# S603X.net
KiCad netlist of a schematic drawn in EAGLE
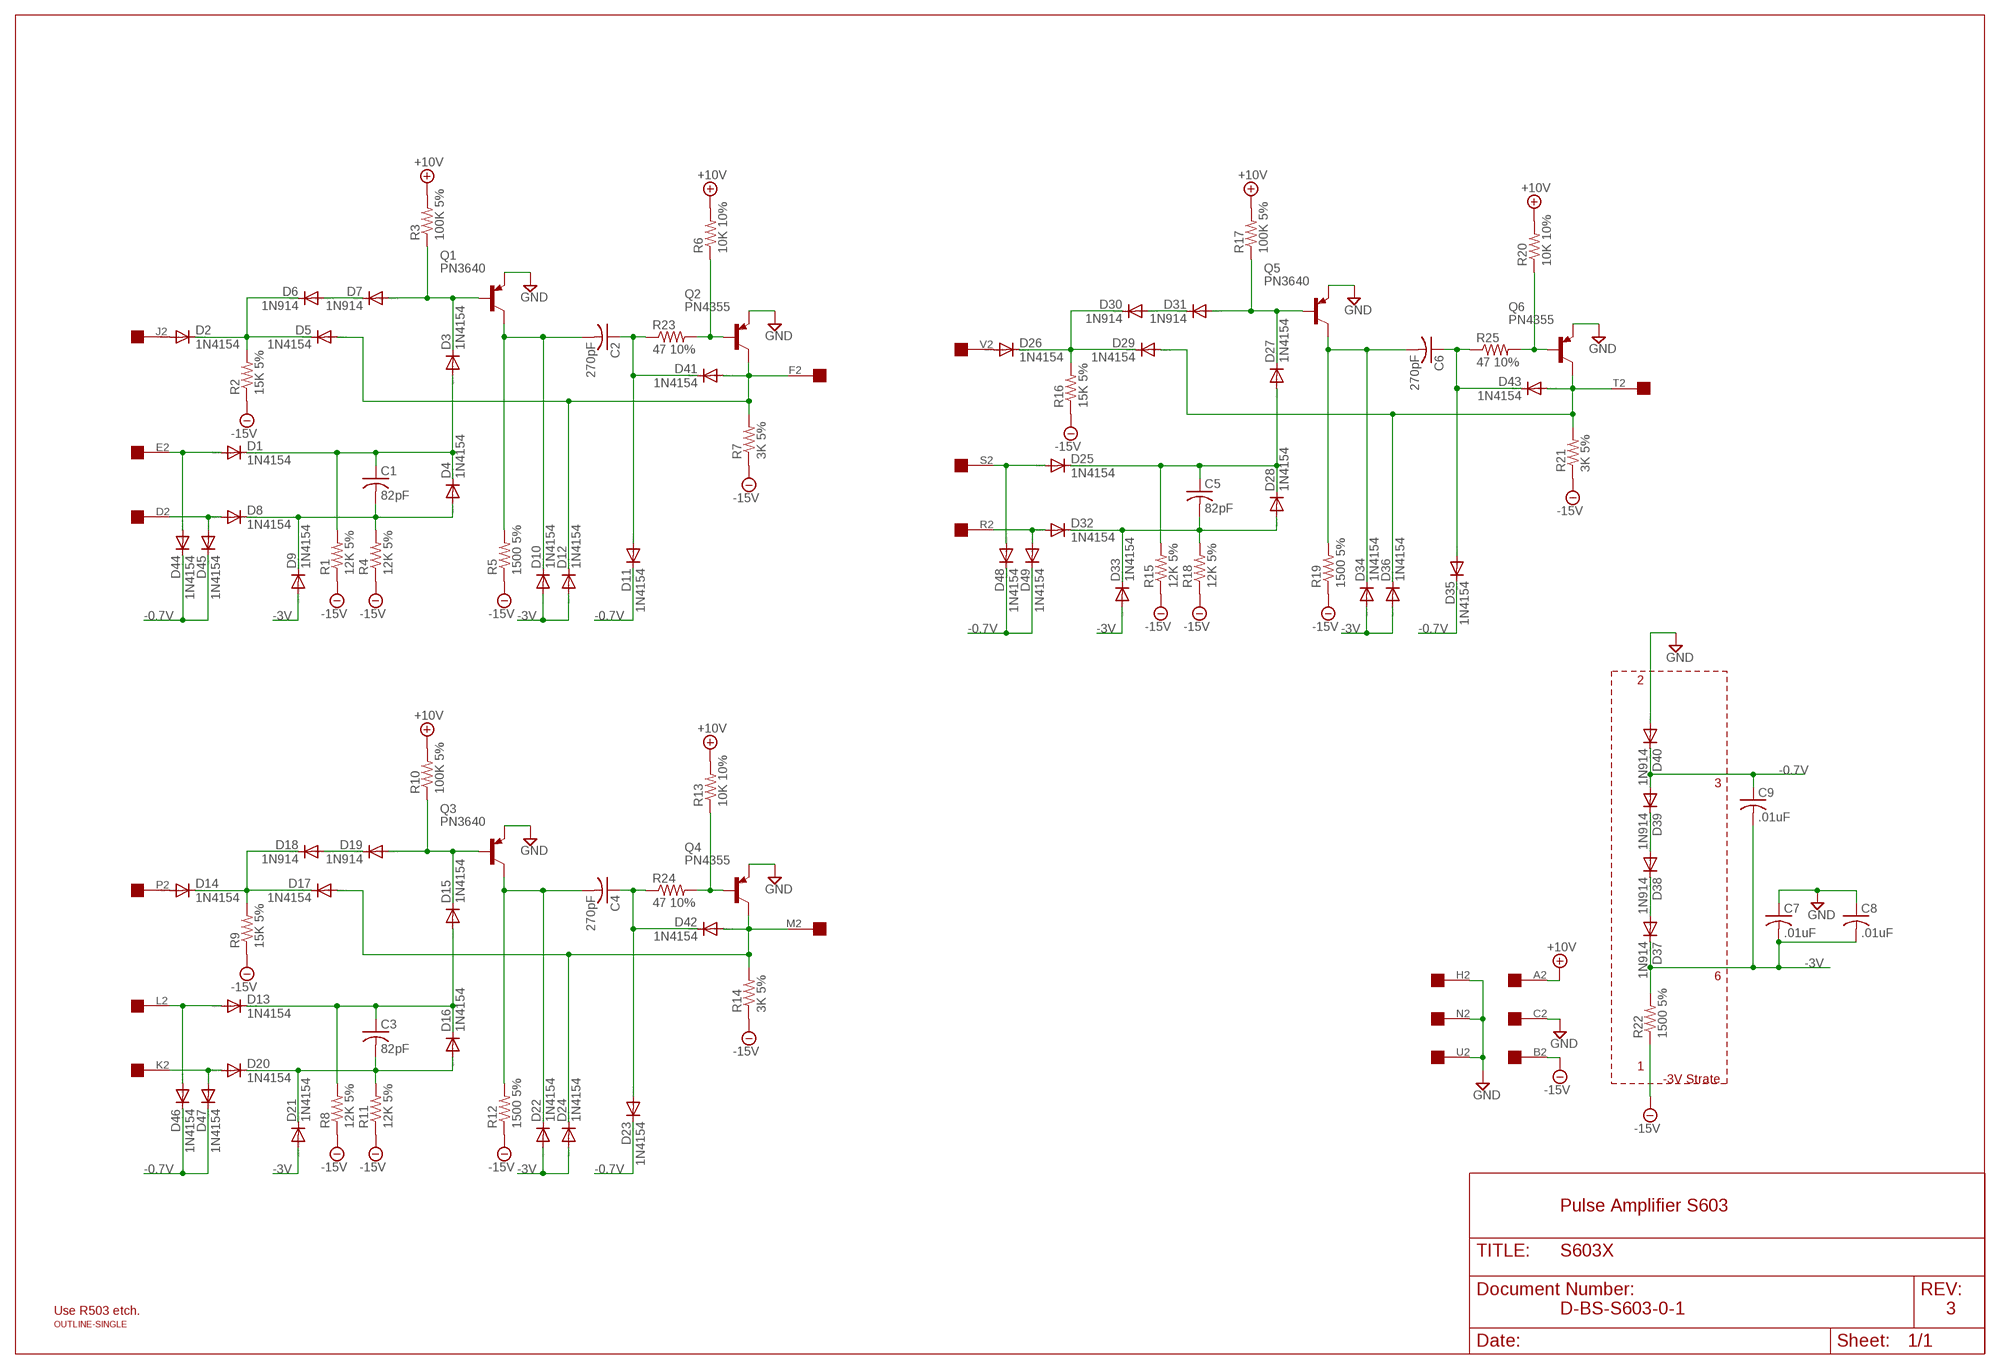
[diagram p0: schematic, sheet 1]

(export (version "E")
  (design (tool "Eeschema 10.0.6"))
  (components
    (comp (ref "C1")
      (value "82pF")
      (footprint "eagle-import:C050-025X075")
      (libsource (lib "eagle-import") (part "C-US050-025X075"))
    )
    (comp (ref "C2")
      (value "270pF")
      (footprint "eagle-import:C050-025X075")
      (libsource (lib "eagle-import") (part "C-US050-025X075"))
    )
    (comp (ref "C3")
      (value "82pF")
      (footprint "eagle-import:C050-025X075")
      (libsource (lib "eagle-import") (part "C-US050-025X075"))
    )
    (comp (ref "C4")
      (value "270pF")
      (footprint "eagle-import:C050-025X075")
      (libsource (lib "eagle-import") (part "C-US050-025X075"))
    )
    (comp (ref "C5")
      (value "82pF")
      (footprint "eagle-import:C050-025X075")
      (libsource (lib "eagle-import") (part "C-US050-025X075"))
    )
    (comp (ref "C6")
      (value "270pF")
      (footprint "eagle-import:C050-025X075")
      (libsource (lib "eagle-import") (part "C-US050-025X075"))
    )
    (comp (ref "C7")
      (value ".01uF")
      (footprint "eagle-import:C050-025X075")
      (libsource (lib "eagle-import") (part "C-US050-025X075"))
    )
    (comp (ref "C8")
      (value ".01uF")
      (footprint "eagle-import:C050-025X075")
      (libsource (lib "eagle-import") (part "C-US050-025X075"))
    )
    (comp (ref "C9")
      (value ".01uF")
      (footprint "eagle-import:C050-025X075")
      (libsource (lib "eagle-import") (part "C-US050-025X075"))
    )
    (comp (ref "D1")
      (value "1N4154")
      (footprint "eagle-import:DO35-10")
      (libsource (lib "eagle-import") (part "1N4148DO35-10"))
    )
    (comp (ref "D2")
      (value "1N4154")
      (footprint "eagle-import:DO35-10")
      (libsource (lib "eagle-import") (part "1N4148DO35-10"))
    )
    (comp (ref "D3")
      (value "1N4154")
      (footprint "eagle-import:DO35-10")
      (libsource (lib "eagle-import") (part "1N4148DO35-10"))
    )
    (comp (ref "D4")
      (value "1N4154")
      (footprint "eagle-import:DO35-10")
      (libsource (lib "eagle-import") (part "1N4148DO35-10"))
    )
    (comp (ref "D5")
      (value "1N4154")
      (footprint "eagle-import:DO35-10")
      (libsource (lib "eagle-import") (part "1N4148DO35-10"))
    )
    (comp (ref "D6")
      (value "1N914")
      (footprint "eagle-import:DO35-10")
      (libsource (lib "eagle-import") (part "1N4148DO35-10"))
    )
    (comp (ref "D7")
      (value "1N914")
      (footprint "eagle-import:DO35-10")
      (libsource (lib "eagle-import") (part "1N4148DO35-10"))
    )
    (comp (ref "D8")
      (value "1N4154")
      (footprint "eagle-import:DO35-10")
      (libsource (lib "eagle-import") (part "1N4148DO35-10"))
    )
    (comp (ref "D9")
      (value "1N4154")
      (footprint "eagle-import:DO35-10")
      (libsource (lib "eagle-import") (part "1N4148DO35-10"))
    )
    (comp (ref "D10")
      (value "1N4154")
      (footprint "eagle-import:DO35-10")
      (libsource (lib "eagle-import") (part "1N4148DO35-10"))
    )
    (comp (ref "D11")
      (value "1N4154")
      (footprint "eagle-import:DO35-10")
      (libsource (lib "eagle-import") (part "1N4148DO35-10"))
    )
    (comp (ref "D12")
      (value "1N4154")
      (footprint "eagle-import:DO35-10")
      (libsource (lib "eagle-import") (part "1N4148DO35-10"))
    )
    (comp (ref "D13")
      (value "1N4154")
      (footprint "eagle-import:DO35-10")
      (libsource (lib "eagle-import") (part "1N4148DO35-10"))
    )
    (comp (ref "D14")
      (value "1N4154")
      (footprint "eagle-import:DO35-10")
      (libsource (lib "eagle-import") (part "1N4148DO35-10"))
    )
    (comp (ref "D15")
      (value "1N4154")
      (footprint "eagle-import:DO35-10")
      (libsource (lib "eagle-import") (part "1N4148DO35-10"))
    )
    (comp (ref "D16")
      (value "1N4154")
      (footprint "eagle-import:DO35-10")
      (libsource (lib "eagle-import") (part "1N4148DO35-10"))
    )
    (comp (ref "D17")
      (value "1N4154")
      (footprint "eagle-import:DO35-10")
      (libsource (lib "eagle-import") (part "1N4148DO35-10"))
    )
    (comp (ref "D18")
      (value "1N914")
      (footprint "eagle-import:DO35-10")
      (libsource (lib "eagle-import") (part "1N4148DO35-10"))
    )
    (comp (ref "D19")
      (value "1N914")
      (footprint "eagle-import:DO35-10")
      (libsource (lib "eagle-import") (part "1N4148DO35-10"))
    )
    (comp (ref "D20")
      (value "1N4154")
      (footprint "eagle-import:DO35-10")
      (libsource (lib "eagle-import") (part "1N4148DO35-10"))
    )
    (comp (ref "D21")
      (value "1N4154")
      (footprint "eagle-import:DO35-10")
      (libsource (lib "eagle-import") (part "1N4148DO35-10"))
    )
    (comp (ref "D22")
      (value "1N4154")
      (footprint "eagle-import:DO35-10")
      (libsource (lib "eagle-import") (part "1N4148DO35-10"))
    )
    (comp (ref "D23")
      (value "1N4154")
      (footprint "eagle-import:DO35-10")
      (libsource (lib "eagle-import") (part "1N4148DO35-10"))
    )
    (comp (ref "D24")
      (value "1N4154")
      (footprint "eagle-import:DO35-10")
      (libsource (lib "eagle-import") (part "1N4148DO35-10"))
    )
    (comp (ref "D25")
      (value "1N4154")
      (footprint "eagle-import:DO35-10")
      (libsource (lib "eagle-import") (part "1N4148DO35-10"))
    )
    (comp (ref "D26")
      (value "1N4154")
      (footprint "eagle-import:DO35-10")
      (libsource (lib "eagle-import") (part "1N4148DO35-10"))
    )
    (comp (ref "D27")
      (value "1N4154")
      (footprint "eagle-import:DO35-10")
      (libsource (lib "eagle-import") (part "1N4148DO35-10"))
    )
    (comp (ref "D28")
      (value "1N4154")
      (footprint "eagle-import:DO35-10")
      (libsource (lib "eagle-import") (part "1N4148DO35-10"))
    )
    (comp (ref "D29")
      (value "1N4154")
      (footprint "eagle-import:DO35-10")
      (libsource (lib "eagle-import") (part "1N4148DO35-10"))
    )
    (comp (ref "D30")
      (value "1N914")
      (footprint "eagle-import:DO35-10")
      (libsource (lib "eagle-import") (part "1N4148DO35-10"))
    )
    (comp (ref "D31")
      (value "1N914")
      (footprint "eagle-import:DO35-10")
      (libsource (lib "eagle-import") (part "1N4148DO35-10"))
    )
    (comp (ref "D32")
      (value "1N4154")
      (footprint "eagle-import:DO35-10")
      (libsource (lib "eagle-import") (part "1N4148DO35-10"))
    )
    (comp (ref "D33")
      (value "1N4154")
      (footprint "eagle-import:DO35-10")
      (libsource (lib "eagle-import") (part "1N4148DO35-10"))
    )
    (comp (ref "D34")
      (value "1N4154")
      (footprint "eagle-import:DO35-10")
      (libsource (lib "eagle-import") (part "1N4148DO35-10"))
    )
    (comp (ref "D35")
      (value "1N4154")
      (footprint "eagle-import:DO35-10")
      (libsource (lib "eagle-import") (part "1N4148DO35-10"))
    )
    (comp (ref "D36")
      (value "1N4154")
      (footprint "eagle-import:DO35-10")
      (libsource (lib "eagle-import") (part "1N4148DO35-10"))
    )
    (comp (ref "D37")
      (value "1N914")
      (footprint "eagle-import:DO35-10")
      (libsource (lib "eagle-import") (part "1N4148DO35-10"))
    )
    (comp (ref "D38")
      (value "1N914")
      (footprint "eagle-import:DO35-10")
      (libsource (lib "eagle-import") (part "1N4148DO35-10"))
    )
    (comp (ref "D39")
      (value "1N914")
      (footprint "eagle-import:DO35-10")
      (libsource (lib "eagle-import") (part "1N4148DO35-10"))
    )
    (comp (ref "D40")
      (value "1N914")
      (footprint "eagle-import:DO35-10")
      (libsource (lib "eagle-import") (part "1N4148DO35-10"))
    )
    (comp (ref "D41")
      (value "1N4154")
      (footprint "eagle-import:DO35-10")
      (libsource (lib "eagle-import") (part "1N4148DO35-10"))
    )
    (comp (ref "D42")
      (value "1N4154")
      (footprint "eagle-import:DO35-10")
      (libsource (lib "eagle-import") (part "1N4148DO35-10"))
    )
    (comp (ref "D43")
      (value "1N4154")
      (footprint "eagle-import:DO35-10")
      (libsource (lib "eagle-import") (part "1N4148DO35-10"))
    )
    (comp (ref "D44")
      (value "1N4154")
      (footprint "eagle-import:DO35-10")
      (libsource (lib "eagle-import") (part "1N4148DO35-10"))
    )
    (comp (ref "D45")
      (value "1N4154")
      (footprint "eagle-import:DO35-10")
      (libsource (lib "eagle-import") (part "1N4148DO35-10"))
    )
    (comp (ref "D46")
      (value "1N4154")
      (footprint "eagle-import:DO35-10")
      (libsource (lib "eagle-import") (part "1N4148DO35-10"))
    )
    (comp (ref "D47")
      (value "1N4154")
      (footprint "eagle-import:DO35-10")
      (libsource (lib "eagle-import") (part "1N4148DO35-10"))
    )
    (comp (ref "D48")
      (value "1N4154")
      (footprint "eagle-import:DO35-10")
      (libsource (lib "eagle-import") (part "1N4148DO35-10"))
    )
    (comp (ref "D49")
      (value "1N4154")
      (footprint "eagle-import:DO35-10")
      (libsource (lib "eagle-import") (part "1N4148DO35-10"))
    )
    (comp (ref "Q1")
      (value "PN3640")
      (footprint "eagle-import:TO39")
      (libsource (lib "eagle-import") (part "2N2904"))
    )
    (comp (ref "Q2")
      (value "PN4355")
      (footprint "eagle-import:TO39")
      (libsource (lib "eagle-import") (part "2N2904"))
    )
    (comp (ref "Q3")
      (value "PN3640")
      (footprint "eagle-import:TO39")
      (libsource (lib "eagle-import") (part "2N2904"))
    )
    (comp (ref "Q4")
      (value "PN4355")
      (footprint "eagle-import:TO39")
      (libsource (lib "eagle-import") (part "2N2904"))
    )
    (comp (ref "Q5")
      (value "PN3640")
      (footprint "eagle-import:TO39")
      (libsource (lib "eagle-import") (part "2N2904"))
    )
    (comp (ref "Q6")
      (value "PN4355")
      (footprint "eagle-import:TO39")
      (libsource (lib "eagle-import") (part "2N2904"))
    )
    (comp (ref "R1")
      (value "12K 5%")
      (footprint "eagle-import:0207_10")
      (libsource (lib "eagle-import") (part "R-US_0207/10"))
    )
    (comp (ref "R2")
      (value "15K 5%")
      (footprint "eagle-import:0207_10")
      (libsource (lib "eagle-import") (part "R-US_0207/10"))
    )
    (comp (ref "R3")
      (value "100K 5%")
      (footprint "eagle-import:0207_10")
      (libsource (lib "eagle-import") (part "R-US_0207/10"))
    )
    (comp (ref "R4")
      (value "12K 5%")
      (footprint "eagle-import:0207_10")
      (libsource (lib "eagle-import") (part "R-US_0207/10"))
    )
    (comp (ref "R5")
      (value "1500 5%")
      (footprint "eagle-import:0207_10")
      (libsource (lib "eagle-import") (part "R-US_0207/10"))
    )
    (comp (ref "R6")
      (value "10K 10%")
      (footprint "eagle-import:0207_10")
      (libsource (lib "eagle-import") (part "R-US_0207/10"))
    )
    (comp (ref "R7")
      (value "3K 5%")
      (footprint "eagle-import:0207_10")
      (libsource (lib "eagle-import") (part "R-US_0207/10"))
    )
    (comp (ref "R8")
      (value "12K 5%")
      (footprint "eagle-import:0207_10")
      (libsource (lib "eagle-import") (part "R-US_0207/10"))
    )
    (comp (ref "R9")
      (value "15K 5%")
      (footprint "eagle-import:0207_10")
      (libsource (lib "eagle-import") (part "R-US_0207/10"))
    )
    (comp (ref "R10")
      (value "100K 5%")
      (footprint "eagle-import:0207_10")
      (libsource (lib "eagle-import") (part "R-US_0207/10"))
    )
    (comp (ref "R11")
      (value "12K 5%")
      (footprint "eagle-import:0207_10")
      (libsource (lib "eagle-import") (part "R-US_0207/10"))
    )
    (comp (ref "R12")
      (value "1500 5%")
      (footprint "eagle-import:0207_10")
      (libsource (lib "eagle-import") (part "R-US_0207/10"))
    )
    (comp (ref "R13")
      (value "10K 10%")
      (footprint "eagle-import:0207_10")
      (libsource (lib "eagle-import") (part "R-US_0207/10"))
    )
    (comp (ref "R14")
      (value "3K 5%")
      (footprint "eagle-import:0207_10")
      (libsource (lib "eagle-import") (part "R-US_0207/10"))
    )
    (comp (ref "R15")
      (value "12K 5%")
      (footprint "eagle-import:0207_10")
      (libsource (lib "eagle-import") (part "R-US_0207/10"))
    )
    (comp (ref "R16")
      (value "15K 5%")
      (footprint "eagle-import:0207_10")
      (libsource (lib "eagle-import") (part "R-US_0207/10"))
    )
    (comp (ref "R17")
      (value "100K 5%")
      (footprint "eagle-import:0207_10")
      (libsource (lib "eagle-import") (part "R-US_0207/10"))
    )
    (comp (ref "R18")
      (value "12K 5%")
      (footprint "eagle-import:0207_10")
      (libsource (lib "eagle-import") (part "R-US_0207/10"))
    )
    (comp (ref "R19")
      (value "1500 5%")
      (footprint "eagle-import:0207_10")
      (libsource (lib "eagle-import") (part "R-US_0207/10"))
    )
    (comp (ref "R20")
      (value "10K 10%")
      (footprint "eagle-import:0207_10")
      (libsource (lib "eagle-import") (part "R-US_0207/10"))
    )
    (comp (ref "R21")
      (value "3K 5%")
      (footprint "eagle-import:0207_10")
      (libsource (lib "eagle-import") (part "R-US_0207/10"))
    )
    (comp (ref "R22")
      (value "1500 5%")
      (footprint "eagle-import:0207_10")
      (libsource (lib "eagle-import") (part "R-US_0207/10"))
    )
    (comp (ref "R23")
      (value "47 10%")
      (footprint "eagle-import:0207_10")
      (libsource (lib "eagle-import") (part "R-US_0207/10"))
    )
    (comp (ref "R24")
      (value "47 10%")
      (footprint "eagle-import:0207_10")
      (libsource (lib "eagle-import") (part "R-US_0207/10"))
    )
    (comp (ref "R25")
      (value "47 10%")
      (footprint "eagle-import:0207_10")
      (libsource (lib "eagle-import") (part "R-US_0207/10"))
    )
    (comp (ref "U$1")
      (value "OUTLINE-SINGLE")
      (footprint "eagle-import:SINGLE")
      (libsource (lib "eagle-import") (part "OUTLINE-SINGLE"))
    )
    (comp (ref "U$2")
      (value "EDGE-1")
      (footprint "eagle-import:EDGE-CON1")
      (libsource (lib "eagle-import") (part "EDGE-1"))
    )
  )
  (nets
    (net (code "1") (name "+10V") (class "Default")
      (node (ref "R10") (pin "2") (pinfunction "2_2") (pintype "passive"))
      (node (ref "R13") (pin "2") (pinfunction "2_2") (pintype "passive"))
      (node (ref "R17") (pin "2") (pinfunction "2_2") (pintype "passive"))
      (node (ref "R20") (pin "2") (pinfunction "2_2") (pintype "passive"))
      (node (ref "R3") (pin "2") (pinfunction "2_2") (pintype "passive"))
      (node (ref "R6") (pin "2") (pinfunction "2_2") (pintype "passive"))
      (node (ref "U$2") (pin "A2") (pinfunction "1_A2") (pintype "bidirectional"))
    )
    (net (code "2") (name "-15V") (class "Default")
      (node (ref "R1") (pin "1") (pinfunction "1_1") (pintype "passive"))
      (node (ref "R11") (pin "1") (pinfunction "1_1") (pintype "passive"))
      (node (ref "R12") (pin "1") (pinfunction "1_1") (pintype "passive"))
      (node (ref "R14") (pin "1") (pinfunction "1_1") (pintype "passive"))
      (node (ref "R15") (pin "1") (pinfunction "1_1") (pintype "passive"))
      (node (ref "R16") (pin "1") (pinfunction "1_1") (pintype "passive"))
      (node (ref "R18") (pin "1") (pinfunction "1_1") (pintype "passive"))
      (node (ref "R19") (pin "1") (pinfunction "1_1") (pintype "passive"))
      (node (ref "R2") (pin "1") (pinfunction "1_1") (pintype "passive"))
      (node (ref "R21") (pin "1") (pinfunction "1_1") (pintype "passive"))
      (node (ref "R22") (pin "1") (pinfunction "1_1") (pintype "passive"))
      (node (ref "R4") (pin "1") (pinfunction "1_1") (pintype "passive"))
      (node (ref "R5") (pin "1") (pinfunction "1_1") (pintype "passive"))
      (node (ref "R7") (pin "1") (pinfunction "1_1") (pintype "passive"))
      (node (ref "R8") (pin "1") (pinfunction "1_1") (pintype "passive"))
      (node (ref "R9") (pin "1") (pinfunction "1_1") (pintype "passive"))
      (node (ref "U$2") (pin "B2") (pinfunction "1_B2") (pintype "bidirectional"))
    )
    (net (code "3") (name "/-0.7V") (class "Default")
      (node (ref "C9") (pin "1") (pinfunction "1_1") (pintype "passive"))
      (node (ref "D11") (pin "C") (pinfunction "C_C") (pintype "passive"))
      (node (ref "D23") (pin "C") (pinfunction "C_C") (pintype "passive"))
      (node (ref "D35") (pin "C") (pinfunction "C_C") (pintype "passive"))
      (node (ref "D39") (pin "A") (pinfunction "A_A") (pintype "passive"))
      (node (ref "D40") (pin "C") (pinfunction "C_C") (pintype "passive"))
      (node (ref "D44") (pin "C") (pinfunction "C_C") (pintype "passive"))
      (node (ref "D45") (pin "C") (pinfunction "C_C") (pintype "passive"))
      (node (ref "D46") (pin "C") (pinfunction "C_C") (pintype "passive"))
      (node (ref "D47") (pin "C") (pinfunction "C_C") (pintype "passive"))
      (node (ref "D48") (pin "C") (pinfunction "C_C") (pintype "passive"))
      (node (ref "D49") (pin "C") (pinfunction "C_C") (pintype "passive"))
    )
    (net (code "4") (name "/-3V") (class "Default")
      (node (ref "C7") (pin "2") (pinfunction "2_2") (pintype "passive"))
      (node (ref "C8") (pin "2") (pinfunction "2_2") (pintype "passive"))
      (node (ref "C9") (pin "2") (pinfunction "2_2") (pintype "passive"))
      (node (ref "D10") (pin "A") (pinfunction "A_A") (pintype "passive"))
      (node (ref "D12") (pin "A") (pinfunction "A_A") (pintype "passive"))
      (node (ref "D21") (pin "A") (pinfunction "A_A") (pintype "passive"))
      (node (ref "D22") (pin "A") (pinfunction "A_A") (pintype "passive"))
      (node (ref "D24") (pin "A") (pinfunction "A_A") (pintype "passive"))
      (node (ref "D33") (pin "A") (pinfunction "A_A") (pintype "passive"))
      (node (ref "D34") (pin "A") (pinfunction "A_A") (pintype "passive"))
      (node (ref "D36") (pin "A") (pinfunction "A_A") (pintype "passive"))
      (node (ref "D37") (pin "C") (pinfunction "C_C") (pintype "passive"))
      (node (ref "D9") (pin "A") (pinfunction "A_A") (pintype "passive"))
      (node (ref "R22") (pin "2") (pinfunction "2_2") (pintype "passive"))
    )
    (net (code "5") (name "GND") (class "Default")
      (node (ref "C7") (pin "1") (pinfunction "1_1") (pintype "passive"))
      (node (ref "C8") (pin "1") (pinfunction "1_1") (pintype "passive"))
      (node (ref "D40") (pin "A") (pinfunction "A_A") (pintype "passive"))
      (node (ref "Q1") (pin "1") (pinfunction "E_1") (pintype "passive"))
      (node (ref "Q2") (pin "1") (pinfunction "E_1") (pintype "passive"))
      (node (ref "Q3") (pin "1") (pinfunction "E_1") (pintype "passive"))
      (node (ref "Q4") (pin "1") (pinfunction "E_1") (pintype "passive"))
      (node (ref "Q5") (pin "1") (pinfunction "E_1") (pintype "passive"))
      (node (ref "Q6") (pin "1") (pinfunction "E_1") (pintype "passive"))
      (node (ref "U$2") (pin "C2") (pinfunction "1_C2") (pintype "bidirectional"))
      (node (ref "U$2") (pin "H2") (pinfunction "1_H2") (pintype "bidirectional"))
      (node (ref "U$2") (pin "N2") (pinfunction "1_N2") (pintype "bidirectional"))
      (node (ref "U$2") (pin "U2") (pinfunction "1_U2") (pintype "bidirectional"))
    )
    (net (code "6") (name "Net-(C1-Pad1)") (class "Default")
      (node (ref "C1") (pin "1") (pinfunction "1_1") (pintype "passive"))
      (node (ref "D1") (pin "C") (pinfunction "C_C") (pintype "passive"))
      (node (ref "D3") (pin "A") (pinfunction "A_A") (pintype "passive"))
      (node (ref "D4") (pin "C") (pinfunction "C_C") (pintype "passive"))
      (node (ref "R1") (pin "2") (pinfunction "2_2") (pintype "passive"))
    )
    (net (code "7") (name "Net-(C1-Pad2)") (class "Default")
      (node (ref "C1") (pin "2") (pinfunction "2_2") (pintype "passive"))
      (node (ref "D4") (pin "A") (pinfunction "A_A") (pintype "passive"))
      (node (ref "D8") (pin "C") (pinfunction "C_C") (pintype "passive"))
      (node (ref "D9") (pin "C") (pinfunction "C_C") (pintype "passive"))
      (node (ref "R4") (pin "2") (pinfunction "2_2") (pintype "passive"))
    )
    (net (code "8") (name "Net-(C2-Pad1)") (class "Default")
      (node (ref "C2") (pin "1") (pinfunction "1_1") (pintype "passive"))
      (node (ref "D11") (pin "A") (pinfunction "A_A") (pintype "passive"))
      (node (ref "D41") (pin "C") (pinfunction "C_C") (pintype "passive"))
      (node (ref "R23") (pin "1") (pinfunction "1_1") (pintype "passive"))
    )
    (net (code "9") (name "Net-(C3-Pad1)") (class "Default")
      (node (ref "C3") (pin "1") (pinfunction "1_1") (pintype "passive"))
      (node (ref "D13") (pin "C") (pinfunction "C_C") (pintype "passive"))
      (node (ref "D15") (pin "A") (pinfunction "A_A") (pintype "passive"))
      (node (ref "D16") (pin "C") (pinfunction "C_C") (pintype "passive"))
      (node (ref "R8") (pin "2") (pinfunction "2_2") (pintype "passive"))
    )
    (net (code "10") (name "Net-(C3-Pad2)") (class "Default")
      (node (ref "C3") (pin "2") (pinfunction "2_2") (pintype "passive"))
      (node (ref "D16") (pin "A") (pinfunction "A_A") (pintype "passive"))
      (node (ref "D20") (pin "C") (pinfunction "C_C") (pintype "passive"))
      (node (ref "D21") (pin "C") (pinfunction "C_C") (pintype "passive"))
      (node (ref "R11") (pin "2") (pinfunction "2_2") (pintype "passive"))
    )
    (net (code "11") (name "Net-(C4-Pad1)") (class "Default")
      (node (ref "C4") (pin "1") (pinfunction "1_1") (pintype "passive"))
      (node (ref "D23") (pin "A") (pinfunction "A_A") (pintype "passive"))
      (node (ref "D42") (pin "C") (pinfunction "C_C") (pintype "passive"))
      (node (ref "R24") (pin "1") (pinfunction "1_1") (pintype "passive"))
    )
    (net (code "12") (name "Net-(C5-Pad1)") (class "Default")
      (node (ref "C5") (pin "1") (pinfunction "1_1") (pintype "passive"))
      (node (ref "D25") (pin "C") (pinfunction "C_C") (pintype "passive"))
      (node (ref "D27") (pin "A") (pinfunction "A_A") (pintype "passive"))
      (node (ref "D28") (pin "C") (pinfunction "C_C") (pintype "passive"))
      (node (ref "R15") (pin "2") (pinfunction "2_2") (pintype "passive"))
    )
    (net (code "13") (name "Net-(C5-Pad2)") (class "Default")
      (node (ref "C5") (pin "2") (pinfunction "2_2") (pintype "passive"))
      (node (ref "D28") (pin "A") (pinfunction "A_A") (pintype "passive"))
      (node (ref "D32") (pin "C") (pinfunction "C_C") (pintype "passive"))
      (node (ref "D33") (pin "C") (pinfunction "C_C") (pintype "passive"))
      (node (ref "R18") (pin "2") (pinfunction "2_2") (pintype "passive"))
    )
    (net (code "14") (name "Net-(C6-Pad1)") (class "Default")
      (node (ref "C6") (pin "1") (pinfunction "1_1") (pintype "passive"))
      (node (ref "D35") (pin "A") (pinfunction "A_A") (pintype "passive"))
      (node (ref "D43") (pin "C") (pinfunction "C_C") (pintype "passive"))
      (node (ref "R25") (pin "1") (pinfunction "1_1") (pintype "passive"))
    )
    (net (code "15") (name "Net-(D2-PadC)") (class "Default")
      (node (ref "D2") (pin "C") (pinfunction "C_C") (pintype "passive"))
      (node (ref "D5") (pin "C") (pinfunction "C_C") (pintype "passive"))
      (node (ref "D6") (pin "C") (pinfunction "C_C") (pintype "passive"))
      (node (ref "R2") (pin "2") (pinfunction "2_2") (pintype "passive"))
    )
    (net (code "16") (name "Net-(D6-PadA)") (class "Default")
      (node (ref "D6") (pin "A") (pinfunction "A_A") (pintype "passive"))
      (node (ref "D7") (pin "C") (pinfunction "C_C") (pintype "passive"))
    )
    (net (code "17") (name "Net-(D14-PadC)") (class "Default")
      (node (ref "D14") (pin "C") (pinfunction "C_C") (pintype "passive"))
      (node (ref "D17") (pin "C") (pinfunction "C_C") (pintype "passive"))
      (node (ref "D18") (pin "C") (pinfunction "C_C") (pintype "passive"))
      (node (ref "R9") (pin "2") (pinfunction "2_2") (pintype "passive"))
    )
    (net (code "18") (name "Net-(D18-PadA)") (class "Default")
      (node (ref "D18") (pin "A") (pinfunction "A_A") (pintype "passive"))
      (node (ref "D19") (pin "C") (pinfunction "C_C") (pintype "passive"))
    )
    (net (code "19") (name "Net-(D26-PadC)") (class "Default")
      (node (ref "D26") (pin "C") (pinfunction "C_C") (pintype "passive"))
      (node (ref "D29") (pin "C") (pinfunction "C_C") (pintype "passive"))
      (node (ref "D30") (pin "C") (pinfunction "C_C") (pintype "passive"))
      (node (ref "R16") (pin "2") (pinfunction "2_2") (pintype "passive"))
    )
    (net (code "20") (name "Net-(D30-PadA)") (class "Default")
      (node (ref "D30") (pin "A") (pinfunction "A_A") (pintype "passive"))
      (node (ref "D31") (pin "C") (pinfunction "C_C") (pintype "passive"))
    )
    (net (code "21") (name "Net-(D37-PadA)") (class "Default")
      (node (ref "D37") (pin "A") (pinfunction "A_A") (pintype "passive"))
      (node (ref "D38") (pin "C") (pinfunction "C_C") (pintype "passive"))
    )
    (net (code "22") (name "Net-(D38-PadA)") (class "Default")
      (node (ref "D38") (pin "A") (pinfunction "A_A") (pintype "passive"))
      (node (ref "D39") (pin "C") (pinfunction "C_C") (pintype "passive"))
    )
    (net (code "23") (name "Net-(Q1-B)") (class "Default")
      (node (ref "D3") (pin "C") (pinfunction "C_C") (pintype "passive"))
      (node (ref "D7") (pin "A") (pinfunction "A_A") (pintype "passive"))
      (node (ref "Q1") (pin "2") (pinfunction "B_2") (pintype "passive"))
      (node (ref "R3") (pin "1") (pinfunction "1_1") (pintype "passive"))
    )
    (net (code "24") (name "Net-(Q1-C)") (class "Default")
      (node (ref "C2") (pin "2") (pinfunction "2_2") (pintype "passive"))
      (node (ref "D10") (pin "C") (pinfunction "C_C") (pintype "passive"))
      (node (ref "Q1") (pin "3") (pinfunction "C_3") (pintype "passive"))
      (node (ref "R5") (pin "2") (pinfunction "2_2") (pintype "passive"))
    )
    (net (code "25") (name "Net-(Q2-B)") (class "Default")
      (node (ref "Q2") (pin "2") (pinfunction "B_2") (pintype "passive"))
      (node (ref "R23") (pin "2") (pinfunction "2_2") (pintype "passive"))
      (node (ref "R6") (pin "1") (pinfunction "1_1") (pintype "passive"))
    )
    (net (code "26") (name "Net-(Q2-C)") (class "Default")
      (node (ref "D12") (pin "C") (pinfunction "C_C") (pintype "passive"))
      (node (ref "D41") (pin "A") (pinfunction "A_A") (pintype "passive"))
      (node (ref "D5") (pin "A") (pinfunction "A_A") (pintype "passive"))
      (node (ref "Q2") (pin "3") (pinfunction "C_3") (pintype "passive"))
      (node (ref "R7") (pin "2") (pinfunction "2_2") (pintype "passive"))
      (node (ref "U$2") (pin "F2") (pinfunction "1_F2") (pintype "bidirectional"))
    )
    (net (code "27") (name "Net-(Q3-B)") (class "Default")
      (node (ref "D15") (pin "C") (pinfunction "C_C") (pintype "passive"))
      (node (ref "D19") (pin "A") (pinfunction "A_A") (pintype "passive"))
      (node (ref "Q3") (pin "2") (pinfunction "B_2") (pintype "passive"))
      (node (ref "R10") (pin "1") (pinfunction "1_1") (pintype "passive"))
    )
    (net (code "28") (name "Net-(Q3-C)") (class "Default")
      (node (ref "C4") (pin "2") (pinfunction "2_2") (pintype "passive"))
      (node (ref "D22") (pin "C") (pinfunction "C_C") (pintype "passive"))
      (node (ref "Q3") (pin "3") (pinfunction "C_3") (pintype "passive"))
      (node (ref "R12") (pin "2") (pinfunction "2_2") (pintype "passive"))
    )
    (net (code "29") (name "Net-(Q4-B)") (class "Default")
      (node (ref "Q4") (pin "2") (pinfunction "B_2") (pintype "passive"))
      (node (ref "R13") (pin "1") (pinfunction "1_1") (pintype "passive"))
      (node (ref "R24") (pin "2") (pinfunction "2_2") (pintype "passive"))
    )
    (net (code "30") (name "Net-(Q4-C)") (class "Default")
      (node (ref "D17") (pin "A") (pinfunction "A_A") (pintype "passive"))
      (node (ref "D24") (pin "C") (pinfunction "C_C") (pintype "passive"))
      (node (ref "D42") (pin "A") (pinfunction "A_A") (pintype "passive"))
      (node (ref "Q4") (pin "3") (pinfunction "C_3") (pintype "passive"))
      (node (ref "R14") (pin "2") (pinfunction "2_2") (pintype "passive"))
      (node (ref "U$2") (pin "M2") (pinfunction "1_M2") (pintype "bidirectional"))
    )
    (net (code "31") (name "Net-(Q5-B)") (class "Default")
      (node (ref "D27") (pin "C") (pinfunction "C_C") (pintype "passive"))
      (node (ref "D31") (pin "A") (pinfunction "A_A") (pintype "passive"))
      (node (ref "Q5") (pin "2") (pinfunction "B_2") (pintype "passive"))
      (node (ref "R17") (pin "1") (pinfunction "1_1") (pintype "passive"))
    )
    (net (code "32") (name "Net-(Q5-C)") (class "Default")
      (node (ref "C6") (pin "2") (pinfunction "2_2") (pintype "passive"))
      (node (ref "D34") (pin "C") (pinfunction "C_C") (pintype "passive"))
      (node (ref "Q5") (pin "3") (pinfunction "C_3") (pintype "passive"))
      (node (ref "R19") (pin "2") (pinfunction "2_2") (pintype "passive"))
    )
    (net (code "33") (name "Net-(Q6-B)") (class "Default")
      (node (ref "Q6") (pin "2") (pinfunction "B_2") (pintype "passive"))
      (node (ref "R20") (pin "1") (pinfunction "1_1") (pintype "passive"))
      (node (ref "R25") (pin "2") (pinfunction "2_2") (pintype "passive"))
    )
    (net (code "34") (name "Net-(Q6-C)") (class "Default")
      (node (ref "D29") (pin "A") (pinfunction "A_A") (pintype "passive"))
      (node (ref "D36") (pin "C") (pinfunction "C_C") (pintype "passive"))
      (node (ref "D43") (pin "A") (pinfunction "A_A") (pintype "passive"))
      (node (ref "Q6") (pin "3") (pinfunction "C_3") (pintype "passive"))
      (node (ref "R21") (pin "2") (pinfunction "2_2") (pintype "passive"))
      (node (ref "U$2") (pin "T2") (pinfunction "1_T2") (pintype "bidirectional"))
    )
    (net (code "35") (name "Net-(U$2D-1)") (class "Default")
      (node (ref "D45") (pin "A") (pinfunction "A_A") (pintype "passive"))
      (node (ref "D8") (pin "A") (pinfunction "A_A") (pintype "passive"))
      (node (ref "U$2") (pin "D2") (pinfunction "1_D2") (pintype "bidirectional"))
    )
    (net (code "36") (name "Net-(U$2E-1)") (class "Default")
      (node (ref "D1") (pin "A") (pinfunction "A_A") (pintype "passive"))
      (node (ref "D44") (pin "A") (pinfunction "A_A") (pintype "passive"))
      (node (ref "U$2") (pin "E2") (pinfunction "1_E2") (pintype "bidirectional"))
    )
    (net (code "37") (name "Net-(U$2H-1)") (class "Default")
      (node (ref "D2") (pin "A") (pinfunction "A_A") (pintype "passive"))
      (node (ref "U$2") (pin "J2") (pinfunction "1_J2") (pintype "bidirectional"))
    )
    (net (code "38") (name "Net-(U$2I-1)") (class "Default")
      (node (ref "D20") (pin "A") (pinfunction "A_A") (pintype "passive"))
      (node (ref "D47") (pin "A") (pinfunction "A_A") (pintype "passive"))
      (node (ref "U$2") (pin "K2") (pinfunction "1_K2") (pintype "bidirectional"))
    )
    (net (code "39") (name "Net-(U$2J-1)") (class "Default")
      (node (ref "D13") (pin "A") (pinfunction "A_A") (pintype "passive"))
      (node (ref "D46") (pin "A") (pinfunction "A_A") (pintype "passive"))
      (node (ref "U$2") (pin "L2") (pinfunction "1_L2") (pintype "bidirectional"))
    )
    (net (code "40") (name "Net-(U$2M-1)") (class "Default")
      (node (ref "D14") (pin "A") (pinfunction "A_A") (pintype "passive"))
      (node (ref "U$2") (pin "P2") (pinfunction "1_P2") (pintype "bidirectional"))
    )
    (net (code "41") (name "Net-(U$2N-1)") (class "Default")
      (node (ref "D32") (pin "A") (pinfunction "A_A") (pintype "passive"))
      (node (ref "D49") (pin "A") (pinfunction "A_A") (pintype "passive"))
      (node (ref "U$2") (pin "R2") (pinfunction "1_R2") (pintype "bidirectional"))
    )
    (net (code "42") (name "Net-(U$2O-1)") (class "Default")
      (node (ref "D25") (pin "A") (pinfunction "A_A") (pintype "passive"))
      (node (ref "D48") (pin "A") (pinfunction "A_A") (pintype "passive"))
      (node (ref "U$2") (pin "S2") (pinfunction "1_S2") (pintype "bidirectional"))
    )
    (net (code "43") (name "Net-(U$2R-1)") (class "Default")
      (node (ref "D26") (pin "A") (pinfunction "A_A") (pintype "passive"))
      (node (ref "U$2") (pin "V2") (pinfunction "1_V2") (pintype "bidirectional"))
    )
  )
)
